# LCD_RGB.net
KiCad netlist of a schematic drawn in Altium Designer
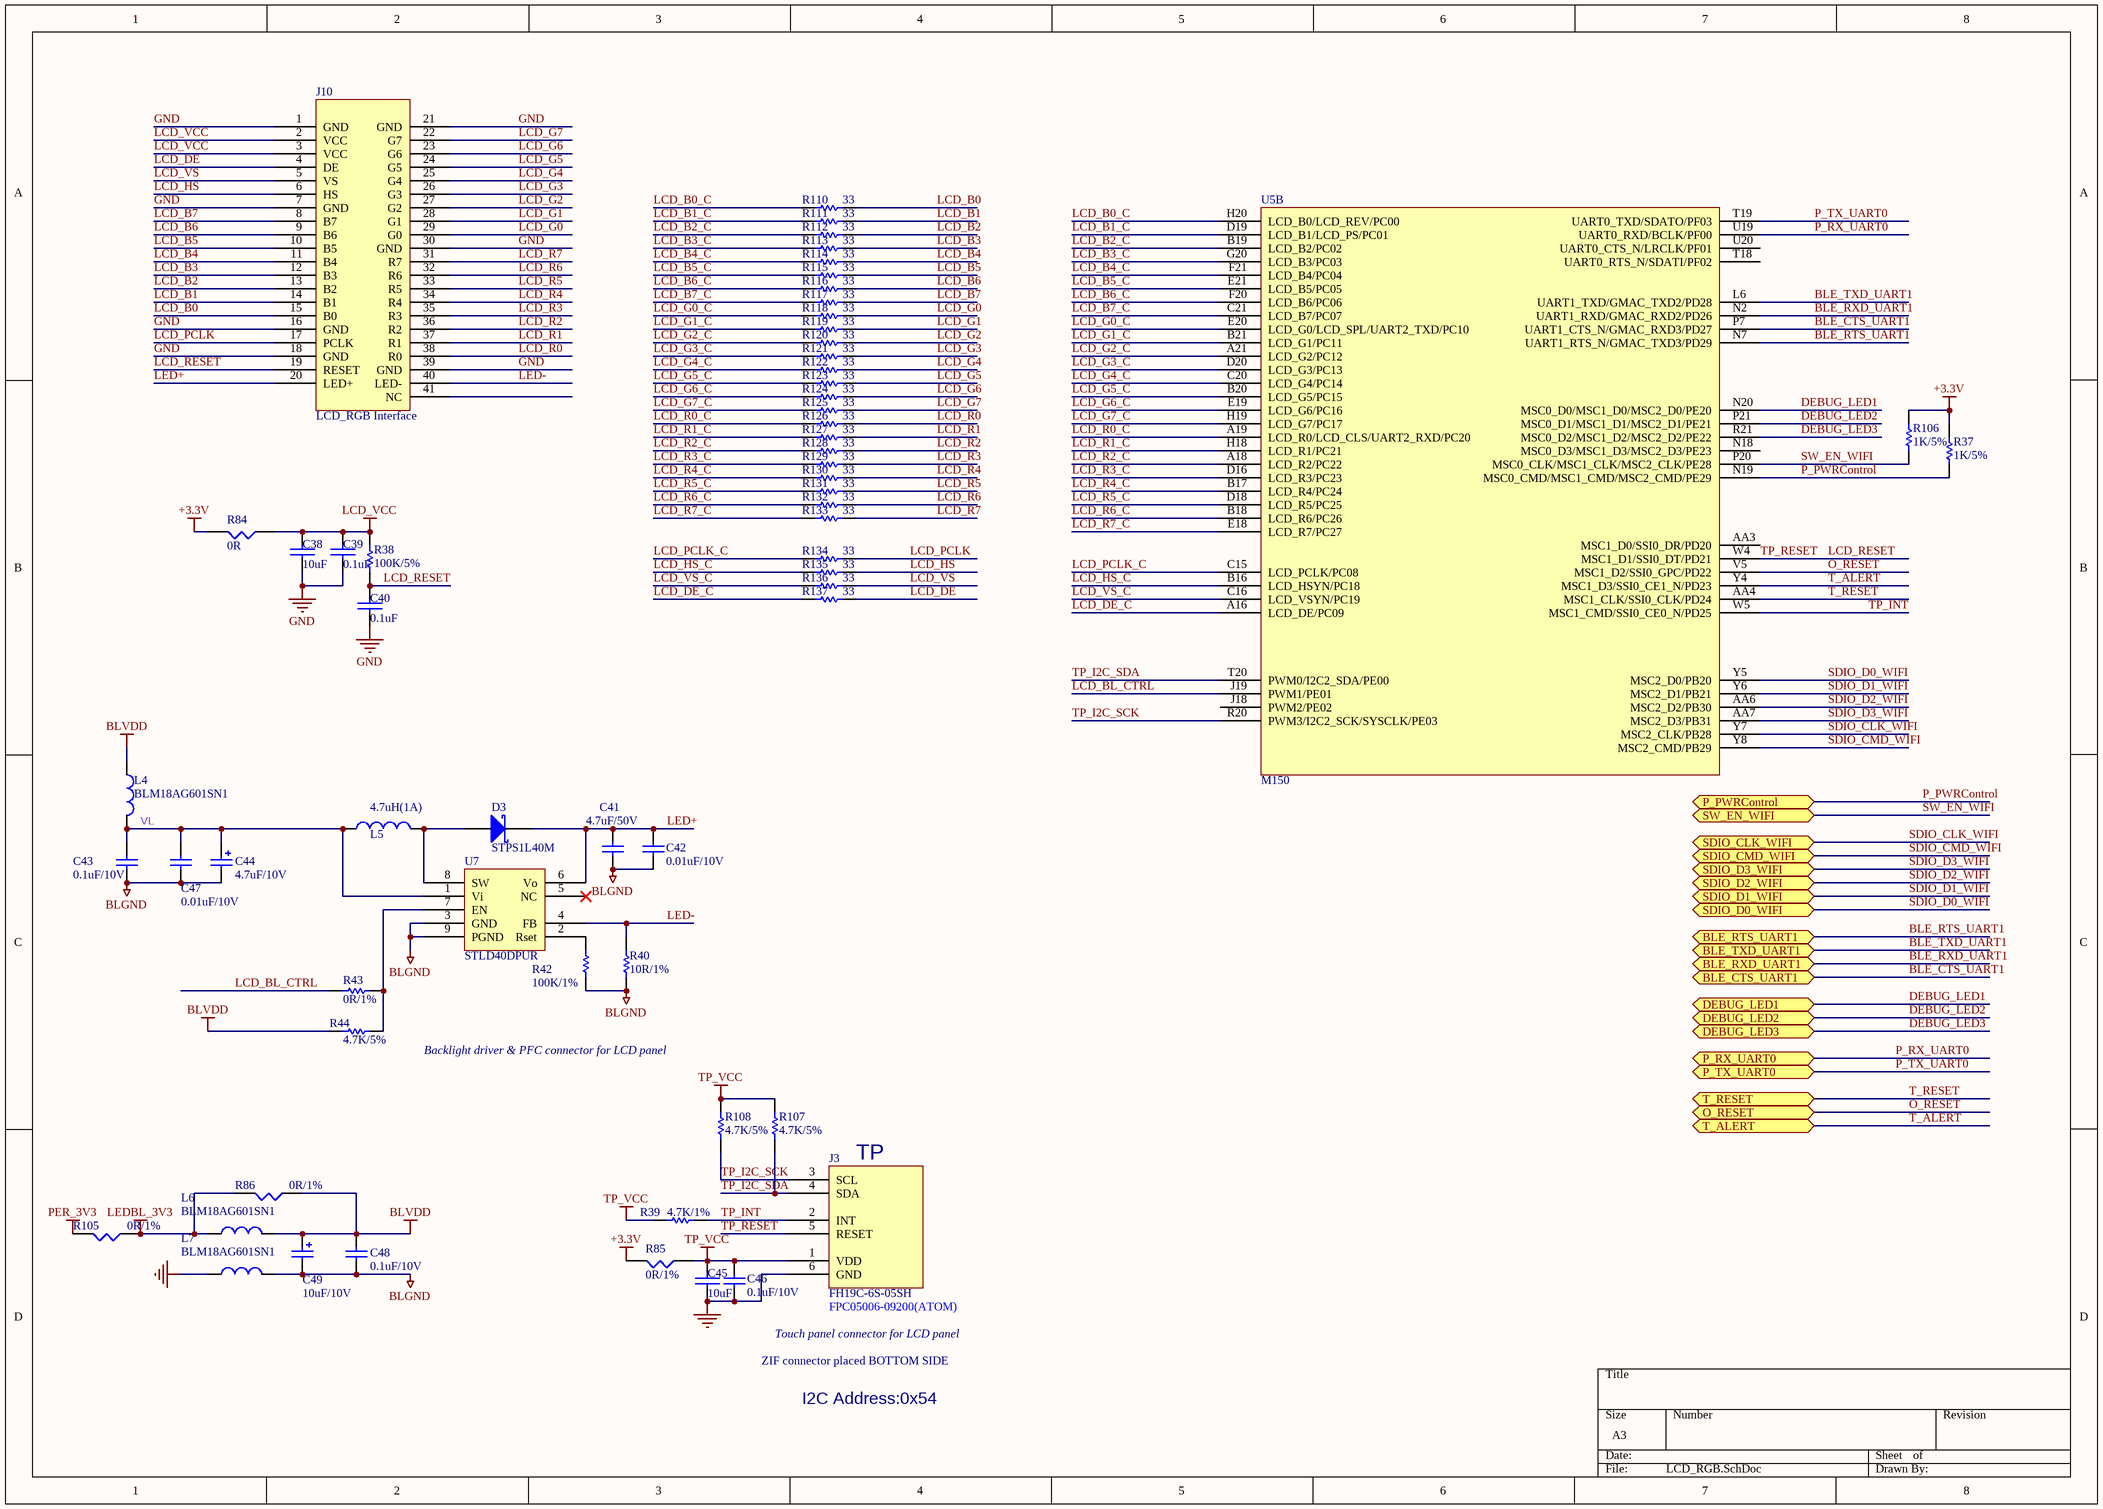
[diagram p0: LCD_RGB.SchDoc]

(export (version "E")
  (design (tool "Eeschema 10.0.6"))
  (components
    (comp (ref "C38")
      (value "10uF")
      (footprint "0402C")
      (description "厂家：Murata，型号：GRM1555C1H120JA01D")
      (libsource (lib "Amber") (part "CAP"))
    )
    (comp (ref "C39")
      (value "0.1uF")
      (footprint "0402C")
      (description "厂家：Murata，型号：GRM1555C1H120JA01D")
      (libsource (lib "Amber") (part "CAP"))
    )
    (comp (ref "C40")
      (value "0.1uF")
      (footprint "0402C")
      (description "厂家：Murata，型号：GRM1555C1H120JA01D")
      (libsource (lib "Amber") (part "CAP"))
    )
    (comp (ref "C41")
      (value "4.7uF/50V")
      (footprint "0603C")
      (description "厂家：Murata，型号：")
      (fields (field (name "PUBLISHER") "Altium Limited"))
      (libsource (lib "Miscellaneous Devices") (part "CAP"))
    )
    (comp (ref "C42")
      (value "0.01uF/10V")
      (footprint "0402C")
      (description "厂家：Murata，型号：")
      (fields (field (name "PUBLISHER") "Altium Limited"))
      (libsource (lib "*") (part "CAP"))
    )
    (comp (ref "C43")
      (value "0.1uF/10V")
      (footprint "0402C")
      (description "Capacitor")
      (fields (field (name "PUBLISHER") "Altium Limited"))
      (libsource (lib "Miscellaneous Devices") (part "CAP"))
    )
    (comp (ref "C44")
      (value "4.7uF/10V")
      (footprint "1206")
      (fields (field (name "PUBLISHER") "Altium Limited"))
      (libsource (lib "Miscellaneous Devices") (part "Cap Pol1"))
    )
    (comp (ref "C45")
      (value "10uF")
      (footprint "0402C")
      (description "厂家：Murata，型号：GRM1555C1H120JA01D")
      (libsource (lib "Amber") (part "CAP"))
    )
    (comp (ref "C46")
      (value "0.1uF/10V")
      (footprint "0402C")
      (description "Capacitor")
      (fields (field (name "PUBLISHER") "Altium Limited"))
      (libsource (lib "Miscellaneous Devices") (part "CAP"))
    )
    (comp (ref "C47")
      (value "0.01uF/10V")
      (footprint "0402C")
      (description "厂家：Murata，型号：")
      (fields (field (name "PUBLISHER") "Altium Limited"))
      (libsource (lib "Miscellaneous Devices") (part "CAP"))
    )
    (comp (ref "C48")
      (value "0.1uF/10V")
      (footprint "0402C")
      (description "Capacitor")
      (fields (field (name "PUBLISHER") "Altium Limited"))
      (libsource (lib "Miscellaneous Devices") (part "Cap"))
    )
    (comp (ref "C49")
      (value "10uF/10V")
      (footprint "TAN-A")
      (description "Polarized Capacitor (Radial)")
      (fields (field (name "PUBLISHER") "Altium Limited"))
      (libsource (lib "Miscellaneous Devices") (part "Cap Pol1"))
    )
    (comp (ref "D3")
      (value "STPS1L40M")
      (footprint "DO-216AA")
      (description "Schottky Diode")
      (fields (field (name "PUBLISHER") "Altium Limited"))
      (libsource (lib "Miscellaneous Devices") (part "D Schottky"))
    )
    (comp (ref "J3")
      (value "FH19C-6S-05SH")
      (footprint "FH19C-6S-0R5SH_FPC_CPT")
      (description "ZIF connector placed bottom side")
      (libsource (lib "MB1166") (part "FH19C-6S-05SH"))
    )
    (comp (ref "J10") (value "LCD_RGB Interface") (libsource (lib "M150") (part "LCD_RGB Interface")))
    (comp (ref "L4")
      (value "BLM18AG601SN1")
      (footprint "0603R")
      (description "厂家：MURATA，型号：BLM18AG601SN1")
      (libsource (lib "Amber") (part "CHOKE"))
    )
    (comp (ref "L5")
      (value "4.7uH(1A)")
      (footprint "1210L")
      (description "Inductor")
      (fields (field (name "PUBLISHER") "Altium Limited"))
      (libsource (lib "Miscellaneous Devices") (part "Inductor"))
    )
    (comp (ref "L6")
      (value "BLM18AG601SN1")
      (footprint "0603R")
      (description "厂家：MURATA，型号：BLM18AG601SN1")
      (libsource (lib "Amber") (part "CHOKE"))
    )
    (comp (ref "L7")
      (value "BLM18AG601SN1")
      (footprint "0603R")
      (description "厂家：MURATA，型号：BLM18AG601SN1")
      (libsource (lib "Amber") (part "CHOKE"))
    )
    (comp (ref "R37")
      (value "1K/5%")
      (footprint "0402R")
      (description "Resistor")
      (fields (field (name "PUBLISHER") "Altium Limited"))
      (libsource (lib "Miscellaneous Devices") (part "Res1"))
    )
    (comp (ref "R38")
      (value "100K/5%")
      (footprint "0402R")
      (description "Resistor")
      (fields (field (name "PUBLISHER") "Altium Limited"))
      (libsource (lib "Miscellaneous Devices") (part "Res1"))
    )
    (comp (ref "R39")
      (value "4.7K/1%")
      (footprint "0402R")
      (description "厂家：Yageo，型号：")
      (fields (field (name "PUBLISHER") "Altium Limited"))
      (libsource (lib "*") (part "Res1"))
    )
    (comp (ref "R40")
      (value "10R/1%")
      (footprint "0402R")
      (description "Resistor")
      (fields (field (name "PUBLISHER") "Altium Limited"))
      (libsource (lib "Miscellaneous Devices") (part "Res1"))
    )
    (comp (ref "R42")
      (value "100K/1%")
      (footprint "0402R")
      (description "Resistor")
      (fields (field (name "PUBLISHER") "Altium Limited"))
      (libsource (lib "Miscellaneous Devices") (part "Res1"))
    )
    (comp (ref "R43")
      (value "0R/1%")
      (footprint "0603R")
      (description "Resistor")
      (fields (field (name "PUBLISHER") "Altium Limited"))
      (libsource (lib "Miscellaneous Devices") (part "Res1"))
    )
    (comp (ref "R44")
      (value "4.7K/5%")
      (footprint "0402R")
      (description "厂家：Yageo，型号：")
      (fields (field (name "PUBLISHER") "Altium Limited"))
      (libsource (lib "Miscellaneous Devices") (part "Res1"))
    )
    (comp (ref "R84")
      (value "0R")
      (footprint "0603R")
      (description "厂家：Yageo，型号：RC0402FR-070RL")
      (libsource (lib "*") (part "RES1"))
    )
    (comp (ref "R85")
      (value "0R/1%")
      (footprint "0603R")
      (description "厂家：Yageo，型号：RC0402FR-070RL")
      (libsource (lib "*") (part "RES1"))
    )
    (comp (ref "R86")
      (value "0R/1%")
      (footprint "0603R")
      (description "厂家：Yageo，型号：RC0402FR-070RL")
      (libsource (lib "*") (part "RES1"))
    )
    (comp (ref "R105")
      (value "0R/1%")
      (footprint "0603R")
      (description "厂家：Yageo，型号：RC0402FR-070RL")
      (libsource (lib "*") (part "RES1"))
    )
    (comp (ref "R106")
      (value "1K/5%")
      (footprint "0402R")
      (description "Resistor")
      (fields (field (name "PUBLISHER") "Altium Limited"))
      (libsource (lib "Miscellaneous Devices") (part "Res1"))
    )
    (comp (ref "R107")
      (value "4.7K/5%")
      (footprint "0402R")
      (description "厂家：Yageo，型号：")
      (fields (field (name "PUBLISHER") "Altium Limited"))
      (libsource (lib "*") (part "Res1"))
    )
    (comp (ref "R108")
      (value "4.7K/5%")
      (footprint "0402R")
      (description "厂家：Yageo，型号：")
      (fields (field (name "PUBLISHER") "Altium Limited"))
      (libsource (lib "*") (part "Res1"))
    )
    (comp (ref "R110")
      (value "33")
      (footprint "0402R")
      (description "Resistor")
      (fields (field (name "PUBLISHER") "Altium Limited"))
      (libsource (lib "Miscellaneous Devices") (part "Res1"))
    )
    (comp (ref "R111")
      (value "33")
      (footprint "0402R")
      (description "Resistor")
      (fields (field (name "PUBLISHER") "Altium Limited"))
      (libsource (lib "Miscellaneous Devices") (part "Res1"))
    )
    (comp (ref "R112")
      (value "33")
      (footprint "0402R")
      (description "Resistor")
      (fields (field (name "PUBLISHER") "Altium Limited"))
      (libsource (lib "Miscellaneous Devices") (part "Res1"))
    )
    (comp (ref "R113")
      (value "33")
      (footprint "0402R")
      (description "Resistor")
      (fields (field (name "PUBLISHER") "Altium Limited"))
      (libsource (lib "Miscellaneous Devices") (part "Res1"))
    )
    (comp (ref "R114")
      (value "33")
      (footprint "0402R")
      (description "Resistor")
      (fields (field (name "PUBLISHER") "Altium Limited"))
      (libsource (lib "Miscellaneous Devices") (part "Res1"))
    )
    (comp (ref "R115")
      (value "33")
      (footprint "0402R")
      (description "Resistor")
      (fields (field (name "PUBLISHER") "Altium Limited"))
      (libsource (lib "Miscellaneous Devices") (part "Res1"))
    )
    (comp (ref "R116")
      (value "33")
      (footprint "0402R")
      (description "Resistor")
      (fields (field (name "PUBLISHER") "Altium Limited"))
      (libsource (lib "Miscellaneous Devices") (part "Res1"))
    )
    (comp (ref "R117")
      (value "33")
      (footprint "0402R")
      (description "Resistor")
      (fields (field (name "PUBLISHER") "Altium Limited"))
      (libsource (lib "Miscellaneous Devices") (part "Res1"))
    )
    (comp (ref "R118")
      (value "33")
      (footprint "0402R")
      (description "Resistor")
      (fields (field (name "PUBLISHER") "Altium Limited"))
      (libsource (lib "Miscellaneous Devices") (part "Res1"))
    )
    (comp (ref "R119")
      (value "33")
      (footprint "0402R")
      (description "Resistor")
      (fields (field (name "PUBLISHER") "Altium Limited"))
      (libsource (lib "Miscellaneous Devices") (part "Res1"))
    )
    (comp (ref "R120")
      (value "33")
      (footprint "0402R")
      (description "Resistor")
      (fields (field (name "PUBLISHER") "Altium Limited"))
      (libsource (lib "Miscellaneous Devices") (part "Res1"))
    )
    (comp (ref "R121")
      (value "33")
      (footprint "0402R")
      (description "Resistor")
      (fields (field (name "PUBLISHER") "Altium Limited"))
      (libsource (lib "Miscellaneous Devices") (part "Res1"))
    )
    (comp (ref "R122")
      (value "33")
      (footprint "0402R")
      (description "Resistor")
      (fields (field (name "PUBLISHER") "Altium Limited"))
      (libsource (lib "Miscellaneous Devices") (part "Res1"))
    )
    (comp (ref "R123")
      (value "33")
      (footprint "0402R")
      (description "Resistor")
      (fields (field (name "PUBLISHER") "Altium Limited"))
      (libsource (lib "Miscellaneous Devices") (part "Res1"))
    )
    (comp (ref "R124")
      (value "33")
      (footprint "0402R")
      (description "Resistor")
      (fields (field (name "PUBLISHER") "Altium Limited"))
      (libsource (lib "Miscellaneous Devices") (part "Res1"))
    )
    (comp (ref "R125")
      (value "33")
      (footprint "0402R")
      (description "Resistor")
      (fields (field (name "PUBLISHER") "Altium Limited"))
      (libsource (lib "Miscellaneous Devices") (part "Res1"))
    )
    (comp (ref "R126")
      (value "33")
      (footprint "0402R")
      (description "Resistor")
      (fields (field (name "PUBLISHER") "Altium Limited"))
      (libsource (lib "Miscellaneous Devices") (part "Res1"))
    )
    (comp (ref "R127")
      (value "33")
      (footprint "0402R")
      (description "Resistor")
      (fields (field (name "PUBLISHER") "Altium Limited"))
      (libsource (lib "Miscellaneous Devices") (part "Res1"))
    )
    (comp (ref "R128")
      (value "33")
      (footprint "0402R")
      (description "Resistor")
      (fields (field (name "PUBLISHER") "Altium Limited"))
      (libsource (lib "Miscellaneous Devices") (part "Res1"))
    )
    (comp (ref "R129")
      (value "33")
      (footprint "0402R")
      (description "Resistor")
      (fields (field (name "PUBLISHER") "Altium Limited"))
      (libsource (lib "Miscellaneous Devices") (part "Res1"))
    )
    (comp (ref "R130")
      (value "33")
      (footprint "0402R")
      (description "Resistor")
      (fields (field (name "PUBLISHER") "Altium Limited"))
      (libsource (lib "Miscellaneous Devices") (part "Res1"))
    )
    (comp (ref "R131")
      (value "33")
      (footprint "0402R")
      (description "Resistor")
      (fields (field (name "PUBLISHER") "Altium Limited"))
      (libsource (lib "Miscellaneous Devices") (part "Res1"))
    )
    (comp (ref "R132")
      (value "33")
      (footprint "0402R")
      (description "Resistor")
      (fields (field (name "PUBLISHER") "Altium Limited"))
      (libsource (lib "Miscellaneous Devices") (part "Res1"))
    )
    (comp (ref "R133")
      (value "33")
      (footprint "0402R")
      (description "Resistor")
      (fields (field (name "PUBLISHER") "Altium Limited"))
      (libsource (lib "Miscellaneous Devices") (part "Res1"))
    )
    (comp (ref "R134")
      (value "33")
      (footprint "0402R")
      (description "Resistor")
      (fields (field (name "PUBLISHER") "Altium Limited"))
      (libsource (lib "Miscellaneous Devices") (part "Res1"))
    )
    (comp (ref "R135")
      (value "33")
      (footprint "0402R")
      (description "Resistor")
      (fields (field (name "PUBLISHER") "Altium Limited"))
      (libsource (lib "Miscellaneous Devices") (part "Res1"))
    )
    (comp (ref "R136")
      (value "33")
      (footprint "0402R")
      (description "Resistor")
      (fields (field (name "PUBLISHER") "Altium Limited"))
      (libsource (lib "Miscellaneous Devices") (part "Res1"))
    )
    (comp (ref "R137")
      (value "33")
      (footprint "0402R")
      (description "Resistor")
      (fields (field (name "PUBLISHER") "Altium Limited"))
      (libsource (lib "Miscellaneous Devices") (part "Res1"))
    )
    (comp (ref "U5") (value "M150") (footprint "Model Name") (libsource (lib "M150") (part "M150")))
    (comp (ref "U7")
      (value "STLD40DPUR")
      (footprint "SON8_0R65_3X3")
      (libsource (lib "3.2LCD_daughterboard") (part "STLD40DPMR"))
    )
  )
  (nets
    (net (code "1") (name "+3.3V") (class "Default")
      (node (ref "R106") (pin "1") (pinfunction "1_1") (pintype "passive"))
      (node (ref "R37") (pin "1") (pinfunction "1_1") (pintype "passive"))
      (node (ref "R84") (pin "2") (pinfunction "2_2") (pintype "passive"))
      (node (ref "R85") (pin "2") (pinfunction "2_2") (pintype "passive"))
    )
    (net (code "2") (name "/BLE_CTS_UART1") (class "Default")
      (node (ref "U5") (pin "P7") (pinfunction "UART1_CTS_N/GMAC_RXD3/PD27_P7") (pintype "passive"))
    )
    (net (code "3") (name "/BLE_RTS_UART1") (class "Default")
      (node (ref "U5") (pin "N7") (pinfunction "UART1_RTS_N/GMAC_TXD3/PD29_N7") (pintype "passive"))
    )
    (net (code "4") (name "/BLE_RXD_UART1") (class "Default")
      (node (ref "U5") (pin "N2") (pinfunction "UART1_RXD/GMAC_RXD2/PD26_N2") (pintype "passive"))
    )
    (net (code "5") (name "/BLE_TXD_UART1") (class "Default")
      (node (ref "U5") (pin "L6") (pinfunction "UART1_TXD/GMAC_TXD2/PD28_L6") (pintype "passive"))
    )
    (net (code "6") (name "/DEBUG_LED1") (class "Default")
      (node (ref "U5") (pin "N20") (pinfunction "MSC0_D0/MSC1_D0/MSC2_D0/PE20_N20") (pintype "passive"))
    )
    (net (code "7") (name "/DEBUG_LED2") (class "Default")
      (node (ref "U5") (pin "P21") (pinfunction "MSC0_D1/MSC1_D1/MSC2_D1/PE21_P21") (pintype "passive"))
    )
    (net (code "8") (name "/DEBUG_LED3") (class "Default")
      (node (ref "U5") (pin "R21") (pinfunction "MSC0_D2/MSC1_D2/MSC2_D2/PE22_R21") (pintype "passive"))
    )
    (net (code "9") (name "/LCD_B0") (class "Default")
      (node (ref "J10") (pin "15") (pinfunction "B0_15") (pintype "passive"))
      (node (ref "R110") (pin "2") (pinfunction "2_2") (pintype "passive"))
    )
    (net (code "10") (name "/LCD_B0_C") (class "Default")
      (node (ref "R110") (pin "1") (pinfunction "1_1") (pintype "passive"))
      (node (ref "U5") (pin "H20") (pinfunction "LCD_B0/LCD_REV/PC00_H20") (pintype "passive"))
    )
    (net (code "11") (name "/LCD_B1") (class "Default")
      (node (ref "J10") (pin "14") (pinfunction "B1_14") (pintype "passive"))
      (node (ref "R111") (pin "2") (pinfunction "2_2") (pintype "passive"))
    )
    (net (code "12") (name "/LCD_B1_C") (class "Default")
      (node (ref "R111") (pin "1") (pinfunction "1_1") (pintype "passive"))
      (node (ref "U5") (pin "D19") (pinfunction "LCD_B1/LCD_PS/PC01_D19") (pintype "passive"))
    )
    (net (code "13") (name "/LCD_B2") (class "Default")
      (node (ref "J10") (pin "13") (pinfunction "B2_13") (pintype "passive"))
      (node (ref "R112") (pin "2") (pinfunction "2_2") (pintype "passive"))
    )
    (net (code "14") (name "/LCD_B2_C") (class "Default")
      (node (ref "R112") (pin "1") (pinfunction "1_1") (pintype "passive"))
      (node (ref "U5") (pin "B19") (pinfunction "LCD_B2/PC02_B19") (pintype "passive"))
    )
    (net (code "15") (name "/LCD_B3") (class "Default")
      (node (ref "J10") (pin "12") (pinfunction "B3_12") (pintype "passive"))
      (node (ref "R113") (pin "2") (pinfunction "2_2") (pintype "passive"))
    )
    (net (code "16") (name "/LCD_B3_C") (class "Default")
      (node (ref "R113") (pin "1") (pinfunction "1_1") (pintype "passive"))
      (node (ref "U5") (pin "G20") (pinfunction "LCD_B3/PC03_G20") (pintype "passive"))
    )
    (net (code "17") (name "/LCD_B4") (class "Default")
      (node (ref "J10") (pin "11") (pinfunction "B4_11") (pintype "passive"))
      (node (ref "R114") (pin "2") (pinfunction "2_2") (pintype "passive"))
    )
    (net (code "18") (name "/LCD_B4_C") (class "Default")
      (node (ref "R114") (pin "1") (pinfunction "1_1") (pintype "passive"))
      (node (ref "U5") (pin "F21") (pinfunction "LCD_B4/PC04_F21") (pintype "passive"))
    )
    (net (code "19") (name "/LCD_B5") (class "Default")
      (node (ref "J10") (pin "10") (pinfunction "B5_10") (pintype "passive"))
      (node (ref "R115") (pin "2") (pinfunction "2_2") (pintype "passive"))
    )
    (net (code "20") (name "/LCD_B5_C") (class "Default")
      (node (ref "R115") (pin "1") (pinfunction "1_1") (pintype "passive"))
      (node (ref "U5") (pin "E21") (pinfunction "LCD_B5/PC05_E21") (pintype "passive"))
    )
    (net (code "21") (name "/LCD_B6") (class "Default")
      (node (ref "J10") (pin "9") (pinfunction "B6_9") (pintype "passive"))
      (node (ref "R116") (pin "2") (pinfunction "2_2") (pintype "passive"))
    )
    (net (code "22") (name "/LCD_B6_C") (class "Default")
      (node (ref "R116") (pin "1") (pinfunction "1_1") (pintype "passive"))
      (node (ref "U5") (pin "F20") (pinfunction "LCD_B6/PC06_F20") (pintype "passive"))
    )
    (net (code "23") (name "/LCD_B7") (class "Default")
      (node (ref "J10") (pin "8") (pinfunction "B7_8") (pintype "passive"))
      (node (ref "R117") (pin "2") (pinfunction "2_2") (pintype "passive"))
    )
    (net (code "24") (name "/LCD_B7_C") (class "Default")
      (node (ref "R117") (pin "1") (pinfunction "1_1") (pintype "passive"))
      (node (ref "U5") (pin "C21") (pinfunction "LCD_B7/PC07_C21") (pintype "passive"))
    )
    (net (code "25") (name "/LCD_BL_CTRL") (class "Default")
      (node (ref "R43") (pin "2") (pinfunction "2_2") (pintype "passive"))
      (node (ref "U5") (pin "J19") (pinfunction "PWM1/PE01_J19") (pintype "passive"))
    )
    (net (code "26") (name "/LCD_DE") (class "Default")
      (node (ref "J10") (pin "4") (pinfunction "DE_4") (pintype "passive"))
      (node (ref "R137") (pin "2") (pinfunction "2_2") (pintype "passive"))
    )
    (net (code "27") (name "/LCD_DE_C") (class "Default")
      (node (ref "R137") (pin "1") (pinfunction "1_1") (pintype "passive"))
      (node (ref "U5") (pin "A16") (pinfunction "LCD_DE/PC09_A16") (pintype "passive"))
    )
    (net (code "28") (name "/LCD_G0") (class "Default")
      (node (ref "J10") (pin "29") (pinfunction "G0_29") (pintype "passive"))
      (node (ref "R118") (pin "2") (pinfunction "2_2") (pintype "passive"))
    )
    (net (code "29") (name "/LCD_G0_C") (class "Default")
      (node (ref "R118") (pin "1") (pinfunction "1_1") (pintype "passive"))
      (node (ref "U5") (pin "E20") (pinfunction "LCD_G0/LCD_SPL/UART2_TXD/PC10_E20") (pintype "passive"))
    )
    (net (code "30") (name "/LCD_G1") (class "Default")
      (node (ref "J10") (pin "28") (pinfunction "G1_28") (pintype "passive"))
      (node (ref "R119") (pin "2") (pinfunction "2_2") (pintype "passive"))
    )
    (net (code "31") (name "/LCD_G1_C") (class "Default")
      (node (ref "R119") (pin "1") (pinfunction "1_1") (pintype "passive"))
      (node (ref "U5") (pin "B21") (pinfunction "LCD_G1/PC11_B21") (pintype "passive"))
    )
    (net (code "32") (name "/LCD_G2") (class "Default")
      (node (ref "J10") (pin "27") (pinfunction "G2_27") (pintype "passive"))
      (node (ref "R120") (pin "2") (pinfunction "2_2") (pintype "passive"))
    )
    (net (code "33") (name "/LCD_G2_C") (class "Default")
      (node (ref "R120") (pin "1") (pinfunction "1_1") (pintype "passive"))
      (node (ref "U5") (pin "A21") (pinfunction "LCD_G2/PC12_A21") (pintype "passive"))
    )
    (net (code "34") (name "/LCD_G3") (class "Default")
      (node (ref "J10") (pin "26") (pinfunction "G3_26") (pintype "passive"))
      (node (ref "R121") (pin "2") (pinfunction "2_2") (pintype "passive"))
    )
    (net (code "35") (name "/LCD_G3_C") (class "Default")
      (node (ref "R121") (pin "1") (pinfunction "1_1") (pintype "passive"))
      (node (ref "U5") (pin "D20") (pinfunction "LCD_G3/PC13_D20") (pintype "passive"))
    )
    (net (code "36") (name "/LCD_G4") (class "Default")
      (node (ref "J10") (pin "25") (pinfunction "G4_25") (pintype "passive"))
      (node (ref "R122") (pin "2") (pinfunction "2_2") (pintype "passive"))
    )
    (net (code "37") (name "/LCD_G4_C") (class "Default")
      (node (ref "R122") (pin "1") (pinfunction "1_1") (pintype "passive"))
      (node (ref "U5") (pin "C20") (pinfunction "LCD_G4/PC14_C20") (pintype "passive"))
    )
    (net (code "38") (name "/LCD_G5") (class "Default")
      (node (ref "J10") (pin "24") (pinfunction "G5_24") (pintype "passive"))
      (node (ref "R123") (pin "2") (pinfunction "2_2") (pintype "passive"))
    )
    (net (code "39") (name "/LCD_G5_C") (class "Default")
      (node (ref "R123") (pin "1") (pinfunction "1_1") (pintype "passive"))
      (node (ref "U5") (pin "B20") (pinfunction "LCD_G5/PC15_B20") (pintype "passive"))
    )
    (net (code "40") (name "/LCD_G6") (class "Default")
      (node (ref "J10") (pin "23") (pinfunction "G6_23") (pintype "passive"))
      (node (ref "R124") (pin "2") (pinfunction "2_2") (pintype "passive"))
    )
    (net (code "41") (name "/LCD_G6_C") (class "Default")
      (node (ref "R124") (pin "1") (pinfunction "1_1") (pintype "passive"))
      (node (ref "U5") (pin "E19") (pinfunction "LCD_G6/PC16_E19") (pintype "passive"))
    )
    (net (code "42") (name "/LCD_G7") (class "Default")
      (node (ref "J10") (pin "22") (pinfunction "G7_22") (pintype "passive"))
      (node (ref "R125") (pin "2") (pinfunction "2_2") (pintype "passive"))
    )
    (net (code "43") (name "/LCD_G7_C") (class "Default")
      (node (ref "R125") (pin "1") (pinfunction "1_1") (pintype "passive"))
      (node (ref "U5") (pin "H19") (pinfunction "LCD_G7/PC17_H19") (pintype "passive"))
    )
    (net (code "44") (name "/LCD_HS") (class "Default")
      (node (ref "J10") (pin "6") (pinfunction "HS_6") (pintype "passive"))
      (node (ref "R135") (pin "2") (pinfunction "2_2") (pintype "passive"))
    )
    (net (code "45") (name "/LCD_HS_C") (class "Default")
      (node (ref "R135") (pin "1") (pinfunction "1_1") (pintype "passive"))
      (node (ref "U5") (pin "B16") (pinfunction "LCD_HSYN/PC18_B16") (pintype "passive"))
    )
    (net (code "46") (name "/LCD_PCLK") (class "Default")
      (node (ref "J10") (pin "17") (pinfunction "PCLK_17") (pintype "passive"))
      (node (ref "R134") (pin "2") (pinfunction "2_2") (pintype "passive"))
    )
    (net (code "47") (name "/LCD_PCLK_C") (class "Default")
      (node (ref "R134") (pin "1") (pinfunction "1_1") (pintype "passive"))
      (node (ref "U5") (pin "C15") (pinfunction "LCD_PCLK/PC08_C15") (pintype "passive"))
    )
    (net (code "48") (name "/LCD_R0") (class "Default")
      (node (ref "J10") (pin "38") (pinfunction "R0_38") (pintype "passive"))
      (node (ref "R126") (pin "2") (pinfunction "2_2") (pintype "passive"))
    )
    (net (code "49") (name "/LCD_R0_C") (class "Default")
      (node (ref "R126") (pin "1") (pinfunction "1_1") (pintype "passive"))
      (node (ref "U5") (pin "A19") (pinfunction "LCD_R0/LCD_CLS/UART2_RXD/PC20_A19") (pintype "passive"))
    )
    (net (code "50") (name "/LCD_R1") (class "Default")
      (node (ref "J10") (pin "37") (pinfunction "R1_37") (pintype "passive"))
      (node (ref "R127") (pin "2") (pinfunction "2_2") (pintype "passive"))
    )
    (net (code "51") (name "/LCD_R1_C") (class "Default")
      (node (ref "R127") (pin "1") (pinfunction "1_1") (pintype "passive"))
      (node (ref "U5") (pin "H18") (pinfunction "LCD_R1/PC21_H18") (pintype "passive"))
    )
    (net (code "52") (name "/LCD_R2") (class "Default")
      (node (ref "J10") (pin "36") (pinfunction "R2_36") (pintype "passive"))
      (node (ref "R128") (pin "2") (pinfunction "2_2") (pintype "passive"))
    )
    (net (code "53") (name "/LCD_R2_C") (class "Default")
      (node (ref "R128") (pin "1") (pinfunction "1_1") (pintype "passive"))
      (node (ref "U5") (pin "A18") (pinfunction "LCD_R2/PC22_A18") (pintype "passive"))
    )
    (net (code "54") (name "/LCD_R3") (class "Default")
      (node (ref "J10") (pin "35") (pinfunction "R3_35") (pintype "passive"))
      (node (ref "R129") (pin "2") (pinfunction "2_2") (pintype "passive"))
    )
    (net (code "55") (name "/LCD_R3_C") (class "Default")
      (node (ref "R129") (pin "1") (pinfunction "1_1") (pintype "passive"))
      (node (ref "U5") (pin "D16") (pinfunction "LCD_R3/PC23_D16") (pintype "passive"))
    )
    (net (code "56") (name "/LCD_R4") (class "Default")
      (node (ref "J10") (pin "34") (pinfunction "R4_34") (pintype "passive"))
      (node (ref "R130") (pin "2") (pinfunction "2_2") (pintype "passive"))
    )
    (net (code "57") (name "/LCD_R4_C") (class "Default")
      (node (ref "R130") (pin "1") (pinfunction "1_1") (pintype "passive"))
      (node (ref "U5") (pin "B17") (pinfunction "LCD_R4/PC24_B17") (pintype "passive"))
    )
    (net (code "58") (name "/LCD_R5") (class "Default")
      (node (ref "J10") (pin "33") (pinfunction "R5_33") (pintype "passive"))
      (node (ref "R131") (pin "2") (pinfunction "2_2") (pintype "passive"))
    )
    (net (code "59") (name "/LCD_R5_C") (class "Default")
      (node (ref "R131") (pin "1") (pinfunction "1_1") (pintype "passive"))
      (node (ref "U5") (pin "D18") (pinfunction "LCD_R5/PC25_D18") (pintype "passive"))
    )
    (net (code "60") (name "/LCD_R6") (class "Default")
      (node (ref "J10") (pin "32") (pinfunction "R6_32") (pintype "passive"))
      (node (ref "R132") (pin "2") (pinfunction "2_2") (pintype "passive"))
    )
    (net (code "61") (name "/LCD_R6_C") (class "Default")
      (node (ref "R132") (pin "1") (pinfunction "1_1") (pintype "passive"))
      (node (ref "U5") (pin "B18") (pinfunction "LCD_R6/PC26_B18") (pintype "passive"))
    )
    (net (code "62") (name "/LCD_R7") (class "Default")
      (node (ref "J10") (pin "31") (pinfunction "R7_31") (pintype "passive"))
      (node (ref "R133") (pin "2") (pinfunction "2_2") (pintype "passive"))
    )
    (net (code "63") (name "/LCD_R7_C") (class "Default")
      (node (ref "R133") (pin "1") (pinfunction "1_1") (pintype "passive"))
      (node (ref "U5") (pin "E18") (pinfunction "LCD_R7/PC27_E18") (pintype "passive"))
    )
    (net (code "64") (name "/LCD_RESET") (class "Default")
      (node (ref "C40") (pin "2") (pinfunction "2_2") (pintype "passive"))
      (node (ref "J10") (pin "19") (pinfunction "RESET_19") (pintype "passive"))
      (node (ref "J3") (pin "5") (pinfunction "RESET_5") (pintype "passive"))
      (node (ref "R38") (pin "2") (pinfunction "2_2") (pintype "passive"))
      (node (ref "U5") (pin "W4") (pinfunction "MSC1_D1/SSI0_DT/PD21_W4") (pintype "passive"))
    )
    (net (code "65") (name "/LCD_VS") (class "Default")
      (node (ref "J10") (pin "5") (pinfunction "VS_5") (pintype "passive"))
      (node (ref "R136") (pin "2") (pinfunction "2_2") (pintype "passive"))
    )
    (net (code "66") (name "/LCD_VS_C") (class "Default")
      (node (ref "R136") (pin "1") (pinfunction "1_1") (pintype "passive"))
      (node (ref "U5") (pin "C16") (pinfunction "LCD_VSYN/PC19_C16") (pintype "passive"))
    )
    (net (code "67") (name "/LED+") (class "Default")
      (node (ref "C41") (pin "1") (pinfunction "1_1") (pintype "passive"))
      (node (ref "C42") (pin "2") (pinfunction "2_2") (pintype "passive"))
      (node (ref "D3") (pin "2") (pinfunction "K_2") (pintype "passive"))
      (node (ref "J10") (pin "20") (pinfunction "LED+_20") (pintype "passive"))
      (node (ref "U7") (pin "6") (pinfunction "Vo_6") (pintype "passive"))
    )
    (net (code "68") (name "/LED-") (class "Default")
      (node (ref "J10") (pin "40") (pinfunction "LED-_40") (pintype "passive"))
      (node (ref "R40") (pin "2") (pinfunction "2_2") (pintype "passive"))
      (node (ref "U7") (pin "4") (pinfunction "FB_4") (pintype "passive"))
    )
    (net (code "69") (name "/O_RESET") (class "Default")
      (node (ref "U5") (pin "V5") (pinfunction "MSC1_D2/SSI0_GPC/PD22_V5") (pintype "passive"))
    )
    (net (code "70") (name "/P_PWRControl") (class "Default")
      (node (ref "R37") (pin "2") (pinfunction "2_2") (pintype "passive"))
      (node (ref "U5") (pin "N19") (pinfunction "MSC0_CMD/MSC1_CMD/MSC2_CMD/PE29_N19") (pintype "passive"))
    )
    (net (code "71") (name "/P_RX_UART0") (class "Default")
      (node (ref "U5") (pin "U19") (pinfunction "UART0_RXD/BCLK/PF00_U19") (pintype "passive"))
    )
    (net (code "72") (name "/P_TX_UART0") (class "Default")
      (node (ref "U5") (pin "T19") (pinfunction "UART0_TXD/SDATO/PF03_T19") (pintype "passive"))
    )
    (net (code "73") (name "/SDIO_CLK_WIFI") (class "Default")
      (node (ref "U5") (pin "Y7") (pinfunction "MSC2_CLK/PB28_Y7") (pintype "passive"))
    )
    (net (code "74") (name "/SDIO_CMD_WIFI") (class "Default")
      (node (ref "U5") (pin "Y8") (pinfunction "MSC2_CMD/PB29_Y8") (pintype "passive"))
    )
    (net (code "75") (name "/SDIO_D0_WIFI") (class "Default")
      (node (ref "U5") (pin "Y5") (pinfunction "MSC2_D0/PB20_Y5") (pintype "passive"))
    )
    (net (code "76") (name "/SDIO_D1_WIFI") (class "Default")
      (node (ref "U5") (pin "Y6") (pinfunction "MSC2_D1/PB21_Y6") (pintype "passive"))
    )
    (net (code "77") (name "/SDIO_D2_WIFI") (class "Default")
      (node (ref "U5") (pin "AA6") (pinfunction "MSC2_D2/PB30_AA6") (pintype "passive"))
    )
    (net (code "78") (name "/SDIO_D3_WIFI") (class "Default")
      (node (ref "U5") (pin "AA7") (pinfunction "MSC2_D3/PB31_AA7") (pintype "passive"))
    )
    (net (code "79") (name "/SW_EN_WIFI") (class "Default")
      (node (ref "R106") (pin "2") (pinfunction "2_2") (pintype "passive"))
      (node (ref "U5") (pin "P20") (pinfunction "MSC0_CLK/MSC1_CLK/MSC2_CLK/PE28_P20") (pintype "passive"))
    )
    (net (code "80") (name "/TP_I2C_SCK") (class "Default")
      (node (ref "J3") (pin "3") (pinfunction "SCL_3") (pintype "passive"))
      (node (ref "R108") (pin "1") (pinfunction "1_1") (pintype "passive"))
      (node (ref "U5") (pin "R20") (pinfunction "PWM3/I2C2_SCK/SYSCLK/PE03_R20") (pintype "passive"))
    )
    (net (code "81") (name "/TP_I2C_SDA") (class "Default")
      (node (ref "J3") (pin "4") (pinfunction "SDA_4") (pintype "passive"))
      (node (ref "R107") (pin "1") (pinfunction "1_1") (pintype "passive"))
      (node (ref "U5") (pin "T20") (pinfunction "PWM0/I2C2_SDA/PE00_T20") (pintype "passive"))
    )
    (net (code "82") (name "/TP_INT") (class "Default")
      (node (ref "J3") (pin "2") (pinfunction "INT_2") (pintype "passive"))
      (node (ref "R39") (pin "2") (pinfunction "2_2") (pintype "passive"))
      (node (ref "U5") (pin "W5") (pinfunction "MSC1_CMD/SSI0_CE0_N/PD25_W5") (pintype "passive"))
    )
    (net (code "83") (name "/T_ALERT") (class "Default")
      (node (ref "U5") (pin "Y4") (pinfunction "MSC1_D3/SSI0_CE1_N/PD23_Y4") (pintype "passive"))
    )
    (net (code "84") (name "/T_RESET") (class "Default")
      (node (ref "U5") (pin "AA4") (pinfunction "MSC1_CLK/SSI0_CLK/PD24_AA4") (pintype "passive"))
    )
    (net (code "85") (name "/VL") (class "Default")
      (node (ref "C43") (pin "2") (pinfunction "2_2") (pintype "passive"))
      (node (ref "C44") (pin "1") (pinfunction "1_1") (pintype "passive"))
      (node (ref "C47") (pin "2") (pinfunction "2_2") (pintype "passive"))
      (node (ref "L4") (pin "2") (pinfunction "2_2") (pintype "passive"))
      (node (ref "L5") (pin "1") (pinfunction "1_1") (pintype "passive"))
      (node (ref "U7") (pin "1") (pinfunction "Vi_1") (pintype "passive"))
    )
    (net (code "86") (name "BLGND") (class "Default")
      (node (ref "C41") (pin "2") (pinfunction "2_2") (pintype "passive"))
      (node (ref "C42") (pin "1") (pinfunction "1_1") (pintype "passive"))
      (node (ref "C43") (pin "1") (pinfunction "1_1") (pintype "passive"))
      (node (ref "C44") (pin "2") (pinfunction "2_2") (pintype "passive"))
      (node (ref "C47") (pin "1") (pinfunction "1_1") (pintype "passive"))
      (node (ref "C48") (pin "2") (pinfunction "2_2") (pintype "passive"))
      (node (ref "C49") (pin "2") (pinfunction "2_2") (pintype "passive"))
      (node (ref "L7") (pin "2") (pinfunction "2_2") (pintype "passive"))
      (node (ref "R40") (pin "1") (pinfunction "1_1") (pintype "passive"))
      (node (ref "R42") (pin "2") (pinfunction "2_2") (pintype "passive"))
      (node (ref "U7") (pin "3") (pinfunction "GND_3") (pintype "passive"))
      (node (ref "U7") (pin "9") (pinfunction "PGND_9") (pintype "passive"))
    )
    (net (code "87") (name "BLVDD") (class "Default")
      (node (ref "C48") (pin "1") (pinfunction "1_1") (pintype "passive"))
      (node (ref "C49") (pin "1") (pinfunction "1_1") (pintype "passive"))
      (node (ref "L4") (pin "1") (pinfunction "1_1") (pintype "passive"))
      (node (ref "L6") (pin "2") (pinfunction "2_2") (pintype "passive"))
      (node (ref "R44") (pin "2") (pinfunction "2_2") (pintype "passive"))
      (node (ref "R86") (pin "1") (pinfunction "1_1") (pintype "passive"))
    )
    (net (code "88") (name "GND") (class "Default")
      (node (ref "C38") (pin "1") (pinfunction "1_1") (pintype "passive"))
      (node (ref "C39") (pin "1") (pinfunction "1_1") (pintype "passive"))
      (node (ref "C40") (pin "1") (pinfunction "1_1") (pintype "passive"))
      (node (ref "C45") (pin "1") (pinfunction "1_1") (pintype "passive"))
      (node (ref "C46") (pin "1") (pinfunction "1_1") (pintype "passive"))
      (node (ref "J10") (pin "1") (pinfunction "GND_1") (pintype "passive"))
      (node (ref "J10") (pin "16") (pinfunction "GND_16") (pintype "passive"))
      (node (ref "J10") (pin "18") (pinfunction "GND_18") (pintype "passive"))
      (node (ref "J10") (pin "21") (pinfunction "GND_21") (pintype "passive"))
      (node (ref "J10") (pin "30") (pinfunction "GND_30") (pintype "passive"))
      (node (ref "J10") (pin "39") (pinfunction "GND_39") (pintype "passive"))
      (node (ref "J10") (pin "7") (pinfunction "GND_7") (pintype "passive"))
      (node (ref "J3") (pin "6") (pinfunction "GND_6") (pintype "passive"))
      (node (ref "L7") (pin "1") (pinfunction "1_1") (pintype "passive"))
    )
    (net (code "89") (name "LCD_VCC") (class "Default")
      (node (ref "C38") (pin "2") (pinfunction "2_2") (pintype "passive"))
      (node (ref "C39") (pin "2") (pinfunction "2_2") (pintype "passive"))
      (node (ref "J10") (pin "2") (pinfunction "VCC_2") (pintype "passive"))
      (node (ref "J10") (pin "3") (pinfunction "VCC_3") (pintype "passive"))
      (node (ref "R38") (pin "1") (pinfunction "1_1") (pintype "passive"))
      (node (ref "R84") (pin "1") (pinfunction "1_1") (pintype "passive"))
    )
    (net (code "90") (name "LEDBL_3V3") (class "Default")
      (node (ref "L6") (pin "1") (pinfunction "1_1") (pintype "passive"))
      (node (ref "R105") (pin "1") (pinfunction "1_1") (pintype "passive"))
      (node (ref "R86") (pin "2") (pinfunction "2_2") (pintype "passive"))
    )
    (net (code "91") (name "Net-(D3-A)") (class "Default")
      (node (ref "D3") (pin "1") (pinfunction "A_1") (pintype "passive"))
      (node (ref "L5") (pin "2") (pinfunction "2_2") (pintype "passive"))
      (node (ref "U7") (pin "8") (pinfunction "SW_8") (pintype "passive"))
    )
    (net (code "92") (name "Net-(U7-EN)") (class "Default")
      (node (ref "R43") (pin "1") (pinfunction "1_1") (pintype "passive"))
      (node (ref "R44") (pin "1") (pinfunction "1_1") (pintype "passive"))
      (node (ref "U7") (pin "7") (pinfunction "EN_7") (pintype "passive"))
    )
    (net (code "93") (name "Net-(U7-Rset)") (class "Default")
      (node (ref "R42") (pin "1") (pinfunction "1_1") (pintype "passive"))
      (node (ref "U7") (pin "2") (pinfunction "Rset_2") (pintype "passive"))
    )
    (net (code "94") (name "PER_3V3") (class "Default")
      (node (ref "R105") (pin "2") (pinfunction "2_2") (pintype "passive"))
    )
    (net (code "95") (name "TP_VCC") (class "Default")
      (node (ref "C45") (pin "2") (pinfunction "2_2") (pintype "passive"))
      (node (ref "C46") (pin "2") (pinfunction "2_2") (pintype "passive"))
      (node (ref "J3") (pin "1") (pinfunction "VDD_1") (pintype "passive"))
      (node (ref "R107") (pin "2") (pinfunction "2_2") (pintype "passive"))
      (node (ref "R108") (pin "2") (pinfunction "2_2") (pintype "passive"))
      (node (ref "R39") (pin "1") (pinfunction "1_1") (pintype "passive"))
      (node (ref "R85") (pin "1") (pinfunction "1_1") (pintype "passive"))
    )
    (net (code "96") (name "unconnected-(J10-NC-Pad41)") (class "Default")
      (node (ref "J10") (pin "41") (pinfunction "NC_41") (pintype "passive"))
    )
    (net (code "97") (name "unconnected-(U5B-MSC0_D3{slash}MSC1_D3{slash}MSC2_D3{slash}PE23-PadN18)") (class "Default")
      (node (ref "U5") (pin "N18") (pinfunction "MSC0_D3/MSC1_D3/MSC2_D3/PE23_N18") (pintype "passive"))
    )
    (net (code "98") (name "unconnected-(U5B-MSC1_D0{slash}SSI0_DR{slash}PD20-PadAA3)") (class "Default")
      (node (ref "U5") (pin "AA3") (pinfunction "MSC1_D0/SSI0_DR/PD20_AA3") (pintype "passive"))
    )
    (net (code "99") (name "unconnected-(U5B-PWM2{slash}PE02-PadJ18)") (class "Default")
      (node (ref "U5") (pin "J18") (pinfunction "PWM2/PE02_J18") (pintype "passive"))
    )
    (net (code "100") (name "unconnected-(U5B-UART0_CTS_N{slash}LRCLK{slash}PF01-PadU20)") (class "Default")
      (node (ref "U5") (pin "U20") (pinfunction "UART0_CTS_N/LRCLK/PF01_U20") (pintype "passive"))
    )
    (net (code "101") (name "unconnected-(U5B-UART0_RTS_N{slash}SDATI{slash}PF02-PadT18)") (class "Default")
      (node (ref "U5") (pin "T18") (pinfunction "UART0_RTS_N/SDATI/PF02_T18") (pintype "passive"))
    )
    (net (code "102") (name "unconnected-(U7-NC-Pad5)") (class "Default")
      (node (ref "U7") (pin "5") (pinfunction "NC_5") (pintype "passive+no_connect"))
    )
  )
)
